# Retr3dRT.net
KiCad netlist of a schematic drawn in EAGLE
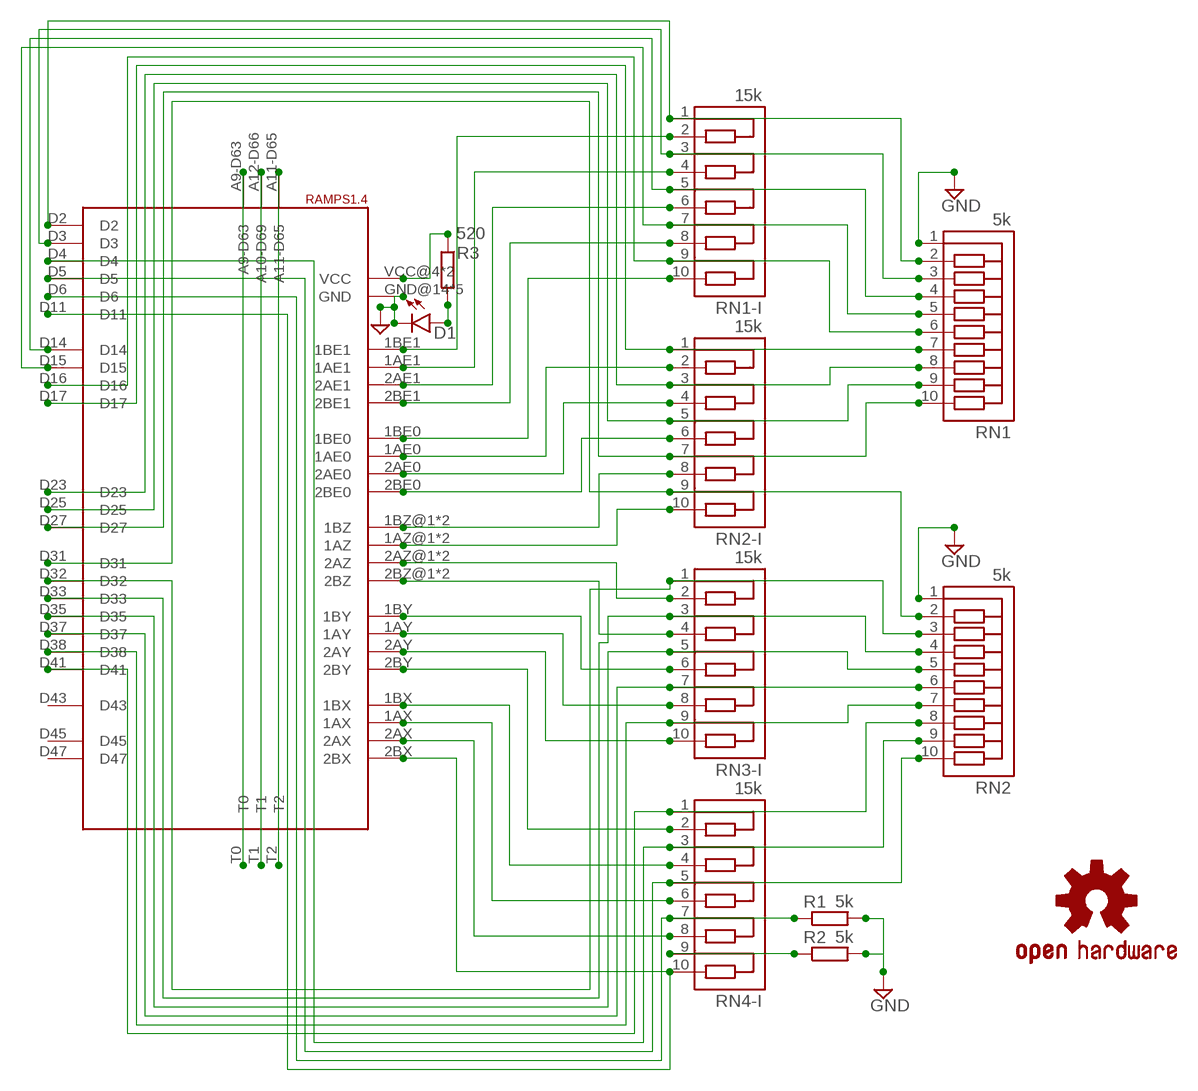
[diagram p0: schematic, sheet 1]

(export (version "E")
  (design (tool "Eeschema 10.0.6"))
  (components
    (comp (ref "D1")
      (value "LED")
      (footprint "eagle-import:LED3MM-NS")
      (libsource (lib "eagle-import") (part "LED-3MM-NO_SILK"))
    )
    (comp (ref "LOGO2")
      (value "OSHW-LOGOL-COPPER")
      (footprint "eagle-import:OSHW-LOGO-L_COPPER")
      (libsource (lib "eagle-import") (part "OSHW-LOGOL-COPPER"))
    )
    (comp (ref "R1")
      (value "5k")
      (footprint "eagle-import:0204_7")
      (libsource (lib "eagle-import") (part "R-EU_0204/7"))
    )
    (comp (ref "R2")
      (value "5k")
      (footprint "eagle-import:0204_7")
      (libsource (lib "eagle-import") (part "R-EU_0204/7"))
    )
    (comp (ref "R3")
      (value "520")
      (footprint "eagle-import:0204_7")
      (libsource (lib "eagle-import") (part "R-EU_0204/7"))
    )
    (comp (ref "RAMPS1.4")
      (value "RAMPS2")
      (footprint "eagle-import:RAMPS2")
      (libsource (lib "eagle-import") (part "RAMPS2"))
    )
    (comp (ref "RN1")
      (value "5k")
      (footprint "eagle-import:RN10")
      (libsource (lib "eagle-import") (part "RN10"))
    )
    (comp (ref "RN1-I")
      (value "15k")
      (footprint "eagle-import:RN10")
      (libsource (lib "eagle-import") (part "RN10-I"))
    )
    (comp (ref "RN2")
      (value "5k")
      (footprint "eagle-import:RN10")
      (libsource (lib "eagle-import") (part "RN10"))
    )
    (comp (ref "RN2-I")
      (value "15k")
      (footprint "eagle-import:RN10")
      (libsource (lib "eagle-import") (part "RN10-I"))
    )
    (comp (ref "RN3-I")
      (value "15k")
      (footprint "eagle-import:RN10")
      (libsource (lib "eagle-import") (part "RN10-I"))
    )
    (comp (ref "RN4-I")
      (value "15k")
      (footprint "eagle-import:RN10")
      (libsource (lib "eagle-import") (part "RN10-I"))
    )
  )
  (nets
    (net (code "1") (name "GND") (class "Default")
      (node (ref "D1") (pin "K") (pinfunction "C_K") (pintype "passive"))
      (node (ref "R1") (pin "2") (pinfunction "2_2") (pintype "passive"))
      (node (ref "R2") (pin "2") (pinfunction "2_2") (pintype "passive"))
      (node (ref "RAMPS1.4") (pin "GND@14") (pinfunction "GND_GND@14") (pintype "power_in"))
      (node (ref "RAMPS1.4") (pin "GND@16") (pinfunction "GND_GND@16") (pintype "power_in"))
      (node (ref "RAMPS1.4") (pin "GND@17") (pinfunction "GND_GND@17") (pintype "power_in"))
      (node (ref "RAMPS1.4") (pin "GND@18") (pinfunction "GND_GND@18") (pintype "power_in"))
      (node (ref "RAMPS1.4") (pin "GND@19") (pinfunction "GND_GND@19") (pintype "power_in"))
      (node (ref "RN1") (pin "1") (pinfunction "1_1") (pintype "passive"))
      (node (ref "RN2") (pin "1") (pinfunction "1_1") (pintype "passive"))
    )
    (net (code "2") (name "Net-(D1-PadA)") (class "Default")
      (node (ref "D1") (pin "A") (pinfunction "A_A") (pintype "passive"))
      (node (ref "R3") (pin "2") (pinfunction "2_2") (pintype "passive"))
    )
    (net (code "3") (name "Net-(R1-Pad1)") (class "Default")
      (node (ref "R1") (pin "1") (pinfunction "1_1") (pintype "passive"))
      (node (ref "RAMPS1.4") (pin "D6") (pinfunction "D6_D6") (pintype "bidirectional"))
      (node (ref "RN4-I") (pin "7") (pinfunction "7_7") (pintype "passive"))
    )
    (net (code "4") (name "Net-(R2-Pad1)") (class "Default")
      (node (ref "R2") (pin "1") (pinfunction "1_1") (pintype "passive"))
      (node (ref "RN4-I") (pin "9") (pinfunction "9_9") (pintype "passive"))
    )
    (net (code "5") (name "Net-(R3-Pad1)") (class "Default")
      (node (ref "R3") (pin "1") (pinfunction "1_1") (pintype "passive"))
      (node (ref "RAMPS1.4") (pin "VCC@4") (pinfunction "VCC_VCC@4") (pintype "power_in"))
      (node (ref "RAMPS1.4") (pin "VCC@6") (pinfunction "VCC_VCC@6") (pintype "power_in"))
    )
    (net (code "6") (name "Net-(RAMPS1.4-1AZ-Pad1AZ@1)") (class "Default")
      (node (ref "RAMPS1.4") (pin "1AZ@1") (pinfunction "1AZ_1AZ@1") (pintype "bidirectional"))
      (node (ref "RAMPS1.4") (pin "1AZ@2") (pinfunction "1AZ_1AZ@2") (pintype "bidirectional"))
      (node (ref "RN2-I") (pin "10") (pinfunction "10_10") (pintype "passive"))
    )
    (net (code "7") (name "Net-(RAMPS1.4-1BZ-Pad1BZ@1)") (class "Default")
      (node (ref "RAMPS1.4") (pin "1BZ@1") (pinfunction "1BZ_1BZ@1") (pintype "bidirectional"))
      (node (ref "RAMPS1.4") (pin "1BZ@2") (pinfunction "1BZ_1BZ@2") (pintype "bidirectional"))
      (node (ref "RN2-I") (pin "8") (pinfunction "8_8") (pintype "passive"))
    )
    (net (code "8") (name "Net-(RAMPS1.4-2AZ-Pad2AZ@1)") (class "Default")
      (node (ref "RAMPS1.4") (pin "2AZ@1") (pinfunction "2AZ_2AZ@1") (pintype "bidirectional"))
      (node (ref "RAMPS1.4") (pin "2AZ@2") (pinfunction "2AZ_2AZ@2") (pintype "bidirectional"))
      (node (ref "RN3-I") (pin "2") (pinfunction "2_2") (pintype "passive"))
    )
    (net (code "9") (name "Net-(RAMPS1.4-2BZ-Pad2BZ@1)") (class "Default")
      (node (ref "RAMPS1.4") (pin "2BZ@1") (pinfunction "2BZ_2BZ@1") (pintype "bidirectional"))
      (node (ref "RAMPS1.4") (pin "2BZ@2") (pinfunction "2BZ_2BZ@2") (pintype "bidirectional"))
      (node (ref "RN3-I") (pin "4") (pinfunction "4_4") (pintype "passive"))
    )
    (net (code "10") (name "Net-(RAMPS1.4-A10-D69)") (class "Default")
      (node (ref "RAMPS1.4") (pin "A12-D66") (pinfunction "A10-D69_A12-D66") (pintype "bidirectional"))
      (node (ref "RAMPS1.4") (pin "T1") (pinfunction "T1_T1") (pintype "bidirectional"))
    )
    (net (code "11") (name "Net-(RAMPS1.4-Pad1AE0)") (class "Default")
      (node (ref "RAMPS1.4") (pin "1AE0") (pinfunction "1AE0_1AE0") (pintype "bidirectional"))
      (node (ref "RN2-I") (pin "2") (pinfunction "2_2") (pintype "passive"))
    )
    (net (code "12") (name "Net-(RAMPS1.4-Pad1AE1)") (class "Default")
      (node (ref "RAMPS1.4") (pin "1AE1") (pinfunction "1AE1_1AE1") (pintype "bidirectional"))
      (node (ref "RN1-I") (pin "4") (pinfunction "4_4") (pintype "passive"))
    )
    (net (code "13") (name "Net-(RAMPS1.4-Pad1AX)") (class "Default")
      (node (ref "RAMPS1.4") (pin "1AX") (pinfunction "1AX_1AX") (pintype "bidirectional"))
      (node (ref "RN4-I") (pin "6") (pinfunction "6_6") (pintype "passive"))
    )
    (net (code "14") (name "Net-(RAMPS1.4-Pad1AY)") (class "Default")
      (node (ref "RAMPS1.4") (pin "1AY") (pinfunction "1AY_1AY") (pintype "bidirectional"))
      (node (ref "RN3-I") (pin "8") (pinfunction "8_8") (pintype "passive"))
    )
    (net (code "15") (name "Net-(RAMPS1.4-Pad1BE0)") (class "Default")
      (node (ref "RAMPS1.4") (pin "1BE0") (pinfunction "1BE0_1BE0") (pintype "bidirectional"))
      (node (ref "RN1-I") (pin "10") (pinfunction "10_10") (pintype "passive"))
    )
    (net (code "16") (name "Net-(RAMPS1.4-Pad1BE1)") (class "Default")
      (node (ref "RAMPS1.4") (pin "1BE1") (pinfunction "1BE1_1BE1") (pintype "bidirectional"))
      (node (ref "RN1-I") (pin "2") (pinfunction "2_2") (pintype "passive"))
    )
    (net (code "17") (name "Net-(RAMPS1.4-Pad1BX)") (class "Default")
      (node (ref "RAMPS1.4") (pin "1BX") (pinfunction "1BX_1BX") (pintype "bidirectional"))
      (node (ref "RN4-I") (pin "4") (pinfunction "4_4") (pintype "passive"))
    )
    (net (code "18") (name "Net-(RAMPS1.4-Pad1BY)") (class "Default")
      (node (ref "RAMPS1.4") (pin "1BY") (pinfunction "1BY_1BY") (pintype "bidirectional"))
      (node (ref "RN3-I") (pin "6") (pinfunction "6_6") (pintype "passive"))
    )
    (net (code "19") (name "Net-(RAMPS1.4-Pad2AE0)") (class "Default")
      (node (ref "RAMPS1.4") (pin "2AE0") (pinfunction "2AE0_2AE0") (pintype "bidirectional"))
      (node (ref "RN2-I") (pin "4") (pinfunction "4_4") (pintype "passive"))
    )
    (net (code "20") (name "Net-(RAMPS1.4-Pad2AE1)") (class "Default")
      (node (ref "RAMPS1.4") (pin "2AE1") (pinfunction "2AE1_2AE1") (pintype "bidirectional"))
      (node (ref "RN1-I") (pin "6") (pinfunction "6_6") (pintype "passive"))
    )
    (net (code "21") (name "Net-(RAMPS1.4-Pad2AX)") (class "Default")
      (node (ref "RAMPS1.4") (pin "2AX") (pinfunction "2AX_2AX") (pintype "bidirectional"))
      (node (ref "RN4-I") (pin "8") (pinfunction "8_8") (pintype "passive"))
    )
    (net (code "22") (name "Net-(RAMPS1.4-Pad2AY)") (class "Default")
      (node (ref "RAMPS1.4") (pin "2AY") (pinfunction "2AY_2AY") (pintype "bidirectional"))
      (node (ref "RN3-I") (pin "10") (pinfunction "10_10") (pintype "passive"))
    )
    (net (code "23") (name "Net-(RAMPS1.4-Pad2BE0)") (class "Default")
      (node (ref "RAMPS1.4") (pin "2BE0") (pinfunction "2BE0_2BE0") (pintype "bidirectional"))
      (node (ref "RN2-I") (pin "6") (pinfunction "6_6") (pintype "passive"))
    )
    (net (code "24") (name "Net-(RAMPS1.4-Pad2BE1)") (class "Default")
      (node (ref "RAMPS1.4") (pin "2BE1") (pinfunction "2BE1_2BE1") (pintype "bidirectional"))
      (node (ref "RN1-I") (pin "8") (pinfunction "8_8") (pintype "passive"))
    )
    (net (code "25") (name "Net-(RAMPS1.4-Pad2BX)") (class "Default")
      (node (ref "RAMPS1.4") (pin "2BX") (pinfunction "2BX_2BX") (pintype "bidirectional"))
      (node (ref "RAMPS1.4") (pin "D11") (pinfunction "D11_D11") (pintype "bidirectional"))
      (node (ref "RN4-I") (pin "10") (pinfunction "10_10") (pintype "passive"))
    )
    (net (code "26") (name "Net-(RAMPS1.4-Pad2BY)") (class "Default")
      (node (ref "RAMPS1.4") (pin "2BY") (pinfunction "2BY_2BY") (pintype "bidirectional"))
      (node (ref "RN4-I") (pin "2") (pinfunction "2_2") (pintype "passive"))
    )
    (net (code "27") (name "Net-(RAMPS1.4-PadA9-D63)") (class "Default")
      (node (ref "RAMPS1.4") (pin "A9-D63") (pinfunction "A9-D63_A9-D63") (pintype "bidirectional"))
      (node (ref "RAMPS1.4") (pin "T0") (pinfunction "T0_T0") (pintype "bidirectional"))
    )
    (net (code "28") (name "Net-(RAMPS1.4-PadA11-D65)") (class "Default")
      (node (ref "RAMPS1.4") (pin "A11-D65") (pinfunction "A11-D65_A11-D65") (pintype "bidirectional"))
      (node (ref "RAMPS1.4") (pin "T2") (pinfunction "T2_T2") (pintype "bidirectional"))
    )
    (net (code "29") (name "Net-(RAMPS1.4-PadD2)") (class "Default")
      (node (ref "RAMPS1.4") (pin "D2") (pinfunction "D2_D2") (pintype "bidirectional"))
      (node (ref "RN1") (pin "2") (pinfunction "2_2") (pintype "passive"))
      (node (ref "RN1-I") (pin "1") (pinfunction "1_1") (pintype "passive"))
    )
    (net (code "30") (name "Net-(RAMPS1.4-PadD3)") (class "Default")
      (node (ref "RAMPS1.4") (pin "D3") (pinfunction "D3_D3") (pintype "bidirectional"))
      (node (ref "RN1") (pin "3") (pinfunction "3_3") (pintype "passive"))
      (node (ref "RN1-I") (pin "3") (pinfunction "3_3") (pintype "passive"))
    )
    (net (code "31") (name "Net-(RAMPS1.4-PadD4)") (class "Default")
      (node (ref "RAMPS1.4") (pin "D4") (pinfunction "D4_D4") (pintype "bidirectional"))
      (node (ref "RN2") (pin "9") (pinfunction "9_9") (pintype "passive"))
      (node (ref "RN4-I") (pin "3") (pinfunction "3_3") (pintype "passive"))
    )
    (net (code "32") (name "Net-(RAMPS1.4-PadD5)") (class "Default")
      (node (ref "RAMPS1.4") (pin "D5") (pinfunction "D5_D5") (pintype "bidirectional"))
      (node (ref "RN2") (pin "10") (pinfunction "10_10") (pintype "passive"))
      (node (ref "RN4-I") (pin "5") (pinfunction "5_5") (pintype "passive"))
    )
    (net (code "33") (name "Net-(RAMPS1.4-PadD14)") (class "Default")
      (node (ref "RAMPS1.4") (pin "D14") (pinfunction "D14_D14") (pintype "bidirectional"))
      (node (ref "RN1") (pin "4") (pinfunction "4_4") (pintype "passive"))
      (node (ref "RN1-I") (pin "5") (pinfunction "5_5") (pintype "passive"))
    )
    (net (code "34") (name "Net-(RAMPS1.4-PadD15)") (class "Default")
      (node (ref "RAMPS1.4") (pin "D15") (pinfunction "D15_D15") (pintype "bidirectional"))
      (node (ref "RN1") (pin "5") (pinfunction "5_5") (pintype "passive"))
      (node (ref "RN1-I") (pin "7") (pinfunction "7_7") (pintype "passive"))
    )
    (net (code "35") (name "Net-(RAMPS1.4-PadD16)") (class "Default")
      (node (ref "RAMPS1.4") (pin "D16") (pinfunction "D16_D16") (pintype "bidirectional"))
      (node (ref "RN1") (pin "6") (pinfunction "6_6") (pintype "passive"))
      (node (ref "RN1-I") (pin "9") (pinfunction "9_9") (pintype "passive"))
    )
    (net (code "36") (name "Net-(RAMPS1.4-PadD17)") (class "Default")
      (node (ref "RAMPS1.4") (pin "D17") (pinfunction "D17_D17") (pintype "bidirectional"))
      (node (ref "RN1") (pin "7") (pinfunction "7_7") (pintype "passive"))
      (node (ref "RN2-I") (pin "1") (pinfunction "1_1") (pintype "passive"))
    )
    (net (code "37") (name "Net-(RAMPS1.4-PadD23)") (class "Default")
      (node (ref "RAMPS1.4") (pin "D23") (pinfunction "D23_D23") (pintype "bidirectional"))
      (node (ref "RN1") (pin "8") (pinfunction "8_8") (pintype "passive"))
      (node (ref "RN2-I") (pin "3") (pinfunction "3_3") (pintype "passive"))
    )
    (net (code "38") (name "Net-(RAMPS1.4-PadD25)") (class "Default")
      (node (ref "RAMPS1.4") (pin "D25") (pinfunction "D25_D25") (pintype "bidirectional"))
      (node (ref "RN1") (pin "9") (pinfunction "9_9") (pintype "passive"))
      (node (ref "RN2-I") (pin "5") (pinfunction "5_5") (pintype "passive"))
    )
    (net (code "39") (name "Net-(RAMPS1.4-PadD27)") (class "Default")
      (node (ref "RAMPS1.4") (pin "D27") (pinfunction "D27_D27") (pintype "bidirectional"))
      (node (ref "RN1") (pin "10") (pinfunction "10_10") (pintype "passive"))
      (node (ref "RN2-I") (pin "7") (pinfunction "7_7") (pintype "passive"))
    )
    (net (code "40") (name "Net-(RAMPS1.4-PadD31)") (class "Default")
      (node (ref "RAMPS1.4") (pin "D31") (pinfunction "D31_D31") (pintype "bidirectional"))
      (node (ref "RN2") (pin "2") (pinfunction "2_2") (pintype "passive"))
      (node (ref "RN2-I") (pin "9") (pinfunction "9_9") (pintype "passive"))
    )
    (net (code "41") (name "Net-(RAMPS1.4-PadD32)") (class "Default")
      (node (ref "RAMPS1.4") (pin "D32") (pinfunction "D32_D32") (pintype "bidirectional"))
      (node (ref "RN2") (pin "3") (pinfunction "3_3") (pintype "passive"))
      (node (ref "RN3-I") (pin "1") (pinfunction "1_1") (pintype "passive"))
    )
    (net (code "42") (name "Net-(RAMPS1.4-PadD33)") (class "Default")
      (node (ref "RAMPS1.4") (pin "D33") (pinfunction "D33_D33") (pintype "input"))
      (node (ref "RN2") (pin "4") (pinfunction "4_4") (pintype "passive"))
      (node (ref "RN3-I") (pin "3") (pinfunction "3_3") (pintype "passive"))
    )
    (net (code "43") (name "Net-(RAMPS1.4-PadD35)") (class "Default")
      (node (ref "RAMPS1.4") (pin "D35") (pinfunction "D35_D35") (pintype "bidirectional"))
      (node (ref "RN2") (pin "5") (pinfunction "5_5") (pintype "passive"))
      (node (ref "RN3-I") (pin "5") (pinfunction "5_5") (pintype "passive"))
    )
    (net (code "44") (name "Net-(RAMPS1.4-PadD37)") (class "Default")
      (node (ref "RAMPS1.4") (pin "D37") (pinfunction "D37_D37") (pintype "bidirectional"))
      (node (ref "RN2") (pin "6") (pinfunction "6_6") (pintype "passive"))
      (node (ref "RN3-I") (pin "7") (pinfunction "7_7") (pintype "passive"))
    )
    (net (code "45") (name "Net-(RAMPS1.4-PadD38)") (class "Default")
      (node (ref "RAMPS1.4") (pin "D38") (pinfunction "D38_D38") (pintype "bidirectional"))
      (node (ref "RN2") (pin "7") (pinfunction "7_7") (pintype "passive"))
      (node (ref "RN3-I") (pin "9") (pinfunction "9_9") (pintype "passive"))
    )
    (net (code "46") (name "Net-(RAMPS1.4-PadD41)") (class "Default")
      (node (ref "RAMPS1.4") (pin "D41") (pinfunction "D41_D41") (pintype "bidirectional"))
      (node (ref "RN2") (pin "8") (pinfunction "8_8") (pintype "passive"))
      (node (ref "RN4-I") (pin "1") (pinfunction "1_1") (pintype "passive"))
    )
    (net (code "47") (name "unconnected-(RAMPS1.4-PadD43)") (class "Default")
      (node (ref "RAMPS1.4") (pin "D43") (pinfunction "D43_D43") (pintype "bidirectional"))
    )
    (net (code "48") (name "unconnected-(RAMPS1.4-PadD45)") (class "Default")
      (node (ref "RAMPS1.4") (pin "D45") (pinfunction "D45_D45") (pintype "bidirectional"))
    )
    (net (code "49") (name "unconnected-(RAMPS1.4-PadD47)") (class "Default")
      (node (ref "RAMPS1.4") (pin "D47") (pinfunction "D47_D47") (pintype "bidirectional"))
    )
  )
)
